# BLE-Shield-1_0_0-B.net
KiCad netlist of a schematic drawn in EAGLE
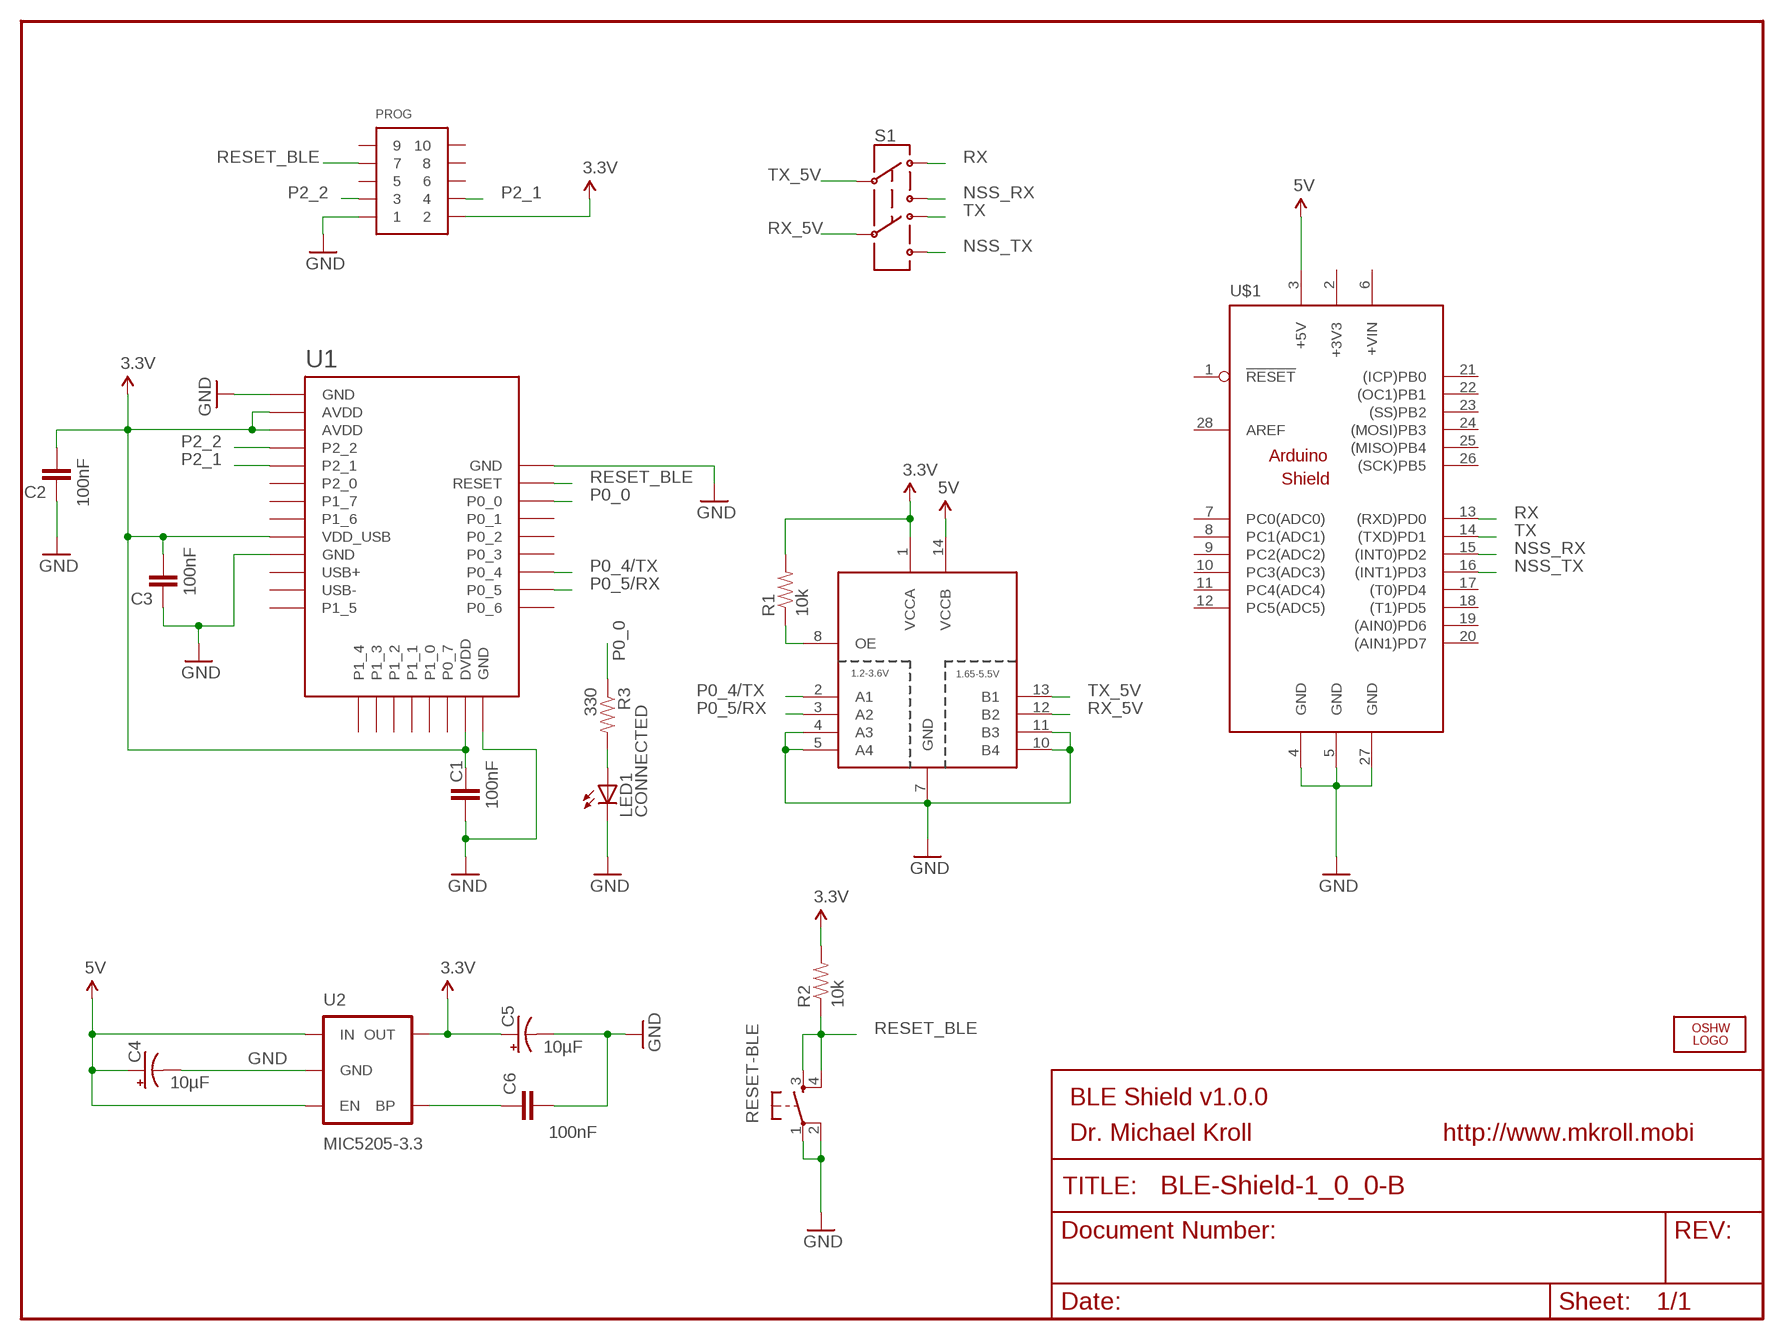
[diagram p0: schematic, sheet 1]

(export (version "E")
  (design (tool "Eeschema 10.0.6"))
  (components
    (comp (ref "C1")
      (value "100nF")
      (footprint "eagle-import:1206")
      (libsource (lib "eagle-import") (part "CAP1206"))
    )
    (comp (ref "C2")
      (value "100nF")
      (footprint "eagle-import:1206")
      (libsource (lib "eagle-import") (part "CAP1206"))
    )
    (comp (ref "C3")
      (value "100nF")
      (footprint "eagle-import:1206")
      (libsource (lib "eagle-import") (part "CAP1206"))
    )
    (comp (ref "C4")
      (value "10µF")
      (footprint "eagle-import:EIA3216")
      (libsource (lib "eagle-import") (part "CAP_POL1206"))
    )
    (comp (ref "C5")
      (value "10µF")
      (footprint "eagle-import:EIA3216")
      (libsource (lib "eagle-import") (part "CAP_POL1206"))
    )
    (comp (ref "C6")
      (value "100nF")
      (footprint "eagle-import:1206")
      (libsource (lib "eagle-import") (part "CAP1206"))
    )
    (comp (ref "LED1")
      (value "CONNECTED")
      (footprint "eagle-import:LED-1206-BLUE")
      (libsource (lib "eagle-import") (part "LED1206-BLUE"))
    )
    (comp (ref "LOGO1")
      (value "LOGO-OSHW-FILLX0200-NT")
      (footprint "eagle-import:OSHW_FILLX200_NOTEXT")
      (libsource (lib "eagle-import") (part "LOGO-OSHW-FILLX0200-NT"))
    )
    (comp (ref "PROG")
      (value "CONN_5-2-FTSH-V")
      (footprint "eagle-import:FTSH-105-DV")
      (libsource (lib "eagle-import") (part "CONN_5-2-FTSH-V"))
    )
    (comp (ref "R1")
      (value "10k")
      (footprint "eagle-import:0805")
      (libsource (lib "eagle-import") (part "RESISTOR0805-RES"))
    )
    (comp (ref "R2")
      (value "10k")
      (footprint "eagle-import:0805")
      (libsource (lib "eagle-import") (part "RESISTOR0805-RES"))
    )
    (comp (ref "R3")
      (value "330")
      (footprint "eagle-import:0805")
      (libsource (lib "eagle-import") (part "RESISTOR0805-RES"))
    )
    (comp (ref "RESET-BLE")
      (value "TAC_SWITCHSMD")
      (footprint "eagle-import:TACTILE_SWITCH_SMD")
      (libsource (lib "eagle-import") (part "TAC_SWITCHSMD"))
    )
    (comp (ref "S1")
      (value "SWITCH-DPDTSMD")
      (footprint "eagle-import:AYZ0202")
      (libsource (lib "eagle-import") (part "SWITCH-DPDTSMD"))
    )
    (comp (ref "U$1")
      (value "ARDUINO_SHIELD")
      (footprint "eagle-import:ARDUINO_SHIELD")
      (libsource (lib "eagle-import") (part "ARDUINO_SHIELD"))
    )
    (comp (ref "U1")
      (value "BLE112-A-VISUAL")
      (footprint "eagle-import:BLE112-A")
      (libsource (lib "eagle-import") (part "BLE112-A-VISUAL"))
    )
    (comp (ref "U2")
      (value "MIC5205-3.3")
      (footprint "eagle-import:SOT23-5")
      (libsource (lib "eagle-import") (part "V_REG_LDOSMD"))
    )
    (comp (ref "U3")
      (value "TXB0104DR")
      (footprint "eagle-import:SO14")
      (libsource (lib "eagle-import") (part "TXB0104DR"))
    )
  )
  (nets
    (net (code "1") (name "/+3V3") (class "Default")
      (node (ref "U$1") (pin "2") (pinfunction "+3V3_2") (pintype "power_in"))
    )
    (net (code "2") (name "/NSS_RX") (class "Default")
      (node (ref "S1") (pin "3") (pinfunction "3_3") (pintype "bidirectional"))
      (node (ref "U$1") (pin "15") (pinfunction "(INT0)PD2_15") (pintype "bidirectional"))
    )
    (net (code "3") (name "/NSS_TX") (class "Default")
      (node (ref "S1") (pin "6") (pinfunction "6_6") (pintype "bidirectional"))
      (node (ref "U$1") (pin "16") (pinfunction "(INT1)PD3_16") (pintype "bidirectional"))
    )
    (net (code "4") (name "/P0_0") (class "Default")
      (node (ref "R3") (pin "1") (pinfunction "1_1") (pintype "passive"))
      (node (ref "U1") (pin "P0_0") (pinfunction "P0_0_P0_0") (pintype "bidirectional"))
    )
    (net (code "5") (name "/P0_4{slash}TX") (class "Default")
      (node (ref "U1") (pin "P0_4") (pinfunction "P0_4_P0_4") (pintype "bidirectional"))
      (node (ref "U3") (pin "2") (pinfunction "A1_2") (pintype "bidirectional"))
    )
    (net (code "6") (name "/P0_5{slash}RX") (class "Default")
      (node (ref "U1") (pin "P0_5") (pinfunction "P0_5_P0_5") (pintype "bidirectional"))
      (node (ref "U3") (pin "3") (pinfunction "A2_3") (pintype "bidirectional"))
    )
    (net (code "7") (name "/P2_1") (class "Default")
      (node (ref "PROG") (pin "4") (pinfunction "4_4") (pintype "bidirectional"))
      (node (ref "U1") (pin "P2_1") (pinfunction "P2_1_P2_1") (pintype "bidirectional"))
    )
    (net (code "8") (name "/P2_2") (class "Default")
      (node (ref "PROG") (pin "3") (pinfunction "3_3") (pintype "bidirectional"))
      (node (ref "U1") (pin "P2_2") (pinfunction "P2_2_P2_2") (pintype "bidirectional"))
    )
    (net (code "9") (name "/RESET_BLE") (class "Default")
      (node (ref "PROG") (pin "7") (pinfunction "7_7") (pintype "bidirectional"))
      (node (ref "R2") (pin "1") (pinfunction "1_1") (pintype "passive"))
      (node (ref "RESET-BLE") (pin "3") (pinfunction "3_3") (pintype "passive"))
      (node (ref "RESET-BLE") (pin "4") (pinfunction "4_4") (pintype "passive"))
      (node (ref "U1") (pin "RESET") (pinfunction "RESET_RESET") (pintype "input"))
    )
    (net (code "10") (name "/RX") (class "Default")
      (node (ref "S1") (pin "1") (pinfunction "1_1") (pintype "bidirectional"))
      (node (ref "U$1") (pin "13") (pinfunction "(RXD)PD0_13") (pintype "bidirectional"))
    )
    (net (code "11") (name "/RX_5V") (class "Default")
      (node (ref "S1") (pin "5") (pinfunction "5_5") (pintype "bidirectional"))
      (node (ref "U3") (pin "12") (pinfunction "B2_12") (pintype "bidirectional"))
    )
    (net (code "12") (name "/TX") (class "Default")
      (node (ref "S1") (pin "4") (pinfunction "4_4") (pintype "bidirectional"))
      (node (ref "U$1") (pin "14") (pinfunction "(TXD)PD1_14") (pintype "bidirectional"))
    )
    (net (code "13") (name "/TX_5V") (class "Default")
      (node (ref "S1") (pin "2") (pinfunction "2_2") (pintype "bidirectional"))
      (node (ref "U3") (pin "13") (pinfunction "B1_13") (pintype "bidirectional"))
    )
    (net (code "14") (name "3.3V") (class "Default")
      (node (ref "C1") (pin "2") (pinfunction "2_2") (pintype "passive"))
      (node (ref "C2") (pin "2") (pinfunction "2_2") (pintype "passive"))
      (node (ref "C3") (pin "2") (pinfunction "2_2") (pintype "passive"))
      (node (ref "C5") (pin "A") (pinfunction "+_A") (pintype "passive"))
      (node (ref "PROG") (pin "2") (pinfunction "2_2") (pintype "bidirectional"))
      (node (ref "R1") (pin "2") (pinfunction "2_2") (pintype "passive"))
      (node (ref "R2") (pin "2") (pinfunction "2_2") (pintype "passive"))
      (node (ref "U1") (pin "AVDD1") (pinfunction "AVDD_AVDD1") (pintype "power_in"))
      (node (ref "U1") (pin "AVDD2") (pinfunction "AVDD_AVDD2") (pintype "power_in"))
      (node (ref "U1") (pin "DVDD") (pinfunction "DVDD_DVDD") (pintype "power_in"))
      (node (ref "U1") (pin "VDD_USB") (pinfunction "VDD_USB_VDD_USB") (pintype "power_in"))
      (node (ref "U2") (pin "5") (pinfunction "OUT_5") (pintype "passive"))
      (node (ref "U3") (pin "1") (pinfunction "VCCA_1") (pintype "bidirectional"))
    )
    (net (code "15") (name "5V") (class "Default")
      (node (ref "C4") (pin "A") (pinfunction "+_A") (pintype "passive"))
      (node (ref "U$1") (pin "3") (pinfunction "+5V_3") (pintype "power_in"))
      (node (ref "U2") (pin "1") (pinfunction "IN_1") (pintype "input"))
      (node (ref "U2") (pin "3") (pinfunction "EN_3") (pintype "input"))
      (node (ref "U3") (pin "14") (pinfunction "VCCB_14") (pintype "bidirectional"))
    )
    (net (code "16") (name "GND") (class "Default")
      (node (ref "C1") (pin "1") (pinfunction "1_1") (pintype "passive"))
      (node (ref "C2") (pin "1") (pinfunction "1_1") (pintype "passive"))
      (node (ref "C3") (pin "1") (pinfunction "1_1") (pintype "passive"))
      (node (ref "C4") (pin "C") (pinfunction "-_C") (pintype "passive"))
      (node (ref "C5") (pin "C") (pinfunction "-_C") (pintype "passive"))
      (node (ref "C6") (pin "2") (pinfunction "2_2") (pintype "passive"))
      (node (ref "LED1") (pin "C") (pinfunction "C_C") (pintype "passive"))
      (node (ref "PROG") (pin "1") (pinfunction "1_1") (pintype "bidirectional"))
      (node (ref "RESET-BLE") (pin "1") (pinfunction "1_1") (pintype "passive"))
      (node (ref "RESET-BLE") (pin "2") (pinfunction "2_2") (pintype "passive"))
      (node (ref "U$1") (pin "27") (pinfunction "GND_27") (pintype "power_in"))
      (node (ref "U$1") (pin "4") (pinfunction "GND_4") (pintype "power_in"))
      (node (ref "U$1") (pin "5") (pinfunction "GND_5") (pintype "power_in"))
      (node (ref "U1") (pin "GND1") (pinfunction "GND_GND1") (pintype "power_in"))
      (node (ref "U1") (pin "GND2") (pinfunction "GND_GND2") (pintype "power_in"))
      (node (ref "U1") (pin "GND3") (pinfunction "GND_GND3") (pintype "power_in"))
      (node (ref "U1") (pin "GND4") (pinfunction "GND_GND4") (pintype "power_in"))
      (node (ref "U2") (pin "2") (pinfunction "GND_2") (pintype "input"))
      (node (ref "U3") (pin "10") (pinfunction "B4_10") (pintype "bidirectional"))
      (node (ref "U3") (pin "11") (pinfunction "B3_11") (pintype "bidirectional"))
      (node (ref "U3") (pin "4") (pinfunction "A3_4") (pintype "bidirectional"))
      (node (ref "U3") (pin "5") (pinfunction "A4_5") (pintype "bidirectional"))
      (node (ref "U3") (pin "7") (pinfunction "GND_7") (pintype "bidirectional"))
    )
    (net (code "17") (name "Net-(LED1-PadA)") (class "Default")
      (node (ref "LED1") (pin "A") (pinfunction "A_A") (pintype "passive"))
      (node (ref "R3") (pin "2") (pinfunction "2_2") (pintype "passive"))
    )
    (net (code "18") (name "Net-(U2-BP)") (class "Default")
      (node (ref "C6") (pin "1") (pinfunction "1_1") (pintype "passive"))
      (node (ref "U2") (pin "4") (pinfunction "BP_4") (pintype "input"))
    )
    (net (code "19") (name "Net-(U3-OE)") (class "Default")
      (node (ref "R1") (pin "1") (pinfunction "1_1") (pintype "passive"))
      (node (ref "U3") (pin "8") (pinfunction "OE_8") (pintype "bidirectional"))
    )
    (net (code "20") (name "unconnected-(PROG-Pad5)") (class "Default")
      (node (ref "PROG") (pin "5") (pinfunction "5_5") (pintype "bidirectional"))
    )
    (net (code "21") (name "unconnected-(PROG-Pad6)") (class "Default")
      (node (ref "PROG") (pin "6") (pinfunction "6_6") (pintype "bidirectional"))
    )
    (net (code "22") (name "unconnected-(PROG-Pad8)") (class "Default")
      (node (ref "PROG") (pin "8") (pinfunction "8_8") (pintype "bidirectional"))
    )
    (net (code "23") (name "unconnected-(PROG-Pad9)") (class "Default")
      (node (ref "PROG") (pin "9") (pinfunction "9_9") (pintype "bidirectional"))
    )
    (net (code "24") (name "unconnected-(PROG-Pad10)") (class "Default")
      (node (ref "PROG") (pin "10") (pinfunction "10_10") (pintype "bidirectional"))
    )
    (net (code "25") (name "unconnected-(U$1-(AIN0)PD6-Pad19)") (class "Default")
      (node (ref "U$1") (pin "19") (pinfunction "(AIN0)PD6_19") (pintype "bidirectional"))
    )
    (net (code "26") (name "unconnected-(U$1-(AIN1)PD7-Pad20)") (class "Default")
      (node (ref "U$1") (pin "20") (pinfunction "(AIN1)PD7_20") (pintype "bidirectional"))
    )
    (net (code "27") (name "unconnected-(U$1-(ICP)PB0-Pad21)") (class "Default")
      (node (ref "U$1") (pin "21") (pinfunction "(ICP)PB0_21") (pintype "bidirectional"))
    )
    (net (code "28") (name "unconnected-(U$1-(MISO)PB4-Pad25)") (class "Default")
      (node (ref "U$1") (pin "25") (pinfunction "(MISO)PB4_25") (pintype "bidirectional"))
    )
    (net (code "29") (name "unconnected-(U$1-(MOSI)PB3-Pad24)") (class "Default")
      (node (ref "U$1") (pin "24") (pinfunction "(MOSI)PB3_24") (pintype "bidirectional"))
    )
    (net (code "30") (name "unconnected-(U$1-(OC1)PB1-Pad22)") (class "Default")
      (node (ref "U$1") (pin "22") (pinfunction "(OC1)PB1_22") (pintype "bidirectional"))
    )
    (net (code "31") (name "unconnected-(U$1-(SCK)PB5-Pad26)") (class "Default")
      (node (ref "U$1") (pin "26") (pinfunction "(SCK)PB5_26") (pintype "bidirectional"))
    )
    (net (code "32") (name "unconnected-(U$1-(SS)PB2-Pad23)") (class "Default")
      (node (ref "U$1") (pin "23") (pinfunction "(SS)PB2_23") (pintype "bidirectional"))
    )
    (net (code "33") (name "unconnected-(U$1-(T0)PD4-Pad17)") (class "Default")
      (node (ref "U$1") (pin "17") (pinfunction "(T0)PD4_17") (pintype "bidirectional"))
    )
    (net (code "34") (name "unconnected-(U$1-(T1)PD5-Pad18)") (class "Default")
      (node (ref "U$1") (pin "18") (pinfunction "(T1)PD5_18") (pintype "bidirectional"))
    )
    (net (code "35") (name "unconnected-(U$1-+VIN-Pad6)") (class "Default")
      (node (ref "U$1") (pin "6") (pinfunction "+VIN_6") (pintype "bidirectional"))
    )
    (net (code "36") (name "unconnected-(U$1-AREF-Pad28)") (class "Default")
      (node (ref "U$1") (pin "28") (pinfunction "AREF_28") (pintype "bidirectional"))
    )
    (net (code "37") (name "unconnected-(U$1-PC0(ADC0)-Pad7)") (class "Default")
      (node (ref "U$1") (pin "7") (pinfunction "PC0(ADC0)_7") (pintype "bidirectional"))
    )
    (net (code "38") (name "unconnected-(U$1-PC1(ADC1)-Pad8)") (class "Default")
      (node (ref "U$1") (pin "8") (pinfunction "PC1(ADC1)_8") (pintype "bidirectional"))
    )
    (net (code "39") (name "unconnected-(U$1-PC2(ADC2)-Pad9)") (class "Default")
      (node (ref "U$1") (pin "9") (pinfunction "PC2(ADC2)_9") (pintype "bidirectional"))
    )
    (net (code "40") (name "unconnected-(U$1-PC3(ADC3)-Pad10)") (class "Default")
      (node (ref "U$1") (pin "10") (pinfunction "PC3(ADC3)_10") (pintype "bidirectional"))
    )
    (net (code "41") (name "unconnected-(U$1-PC4(ADC4)-Pad11)") (class "Default")
      (node (ref "U$1") (pin "11") (pinfunction "PC4(ADC4)_11") (pintype "bidirectional"))
    )
    (net (code "42") (name "unconnected-(U$1-PC5(ADC5)-Pad12)") (class "Default")
      (node (ref "U$1") (pin "12") (pinfunction "PC5(ADC5)_12") (pintype "bidirectional"))
    )
    (net (code "43") (name "unconnected-(U$1-~{RESET}-Pad1)") (class "Default")
      (node (ref "U$1") (pin "1") (pinfunction "~{RESET}_1") (pintype "bidirectional"))
    )
    (net (code "44") (name "unconnected-(U1-PadP0_1)") (class "Default")
      (node (ref "U1") (pin "P0_1") (pinfunction "P0_1_P0_1") (pintype "bidirectional"))
    )
    (net (code "45") (name "unconnected-(U1-PadP0_2)") (class "Default")
      (node (ref "U1") (pin "P0_2") (pinfunction "P0_2_P0_2") (pintype "bidirectional"))
    )
    (net (code "46") (name "unconnected-(U1-PadP0_3)") (class "Default")
      (node (ref "U1") (pin "P0_3") (pinfunction "P0_3_P0_3") (pintype "bidirectional"))
    )
    (net (code "47") (name "unconnected-(U1-PadP0_6)") (class "Default")
      (node (ref "U1") (pin "P0_6") (pinfunction "P0_6_P0_6") (pintype "bidirectional"))
    )
    (net (code "48") (name "unconnected-(U1-PadP0_7)") (class "Default")
      (node (ref "U1") (pin "P0_7") (pinfunction "P0_7_P0_7") (pintype "bidirectional"))
    )
    (net (code "49") (name "unconnected-(U1-PadP1_0)") (class "Default")
      (node (ref "U1") (pin "P1_0") (pinfunction "P1_0_P1_0") (pintype "bidirectional"))
    )
    (net (code "50") (name "unconnected-(U1-PadP1_1)") (class "Default")
      (node (ref "U1") (pin "P1_1") (pinfunction "P1_1_P1_1") (pintype "bidirectional"))
    )
    (net (code "51") (name "unconnected-(U1-PadP1_2)") (class "Default")
      (node (ref "U1") (pin "P1_2") (pinfunction "P1_2_P1_2") (pintype "bidirectional"))
    )
    (net (code "52") (name "unconnected-(U1-PadP1_3)") (class "Default")
      (node (ref "U1") (pin "P1_3") (pinfunction "P1_3_P1_3") (pintype "bidirectional"))
    )
    (net (code "53") (name "unconnected-(U1-PadP1_4)") (class "Default")
      (node (ref "U1") (pin "P1_4") (pinfunction "P1_4_P1_4") (pintype "bidirectional"))
    )
    (net (code "54") (name "unconnected-(U1-PadP1_5)") (class "Default")
      (node (ref "U1") (pin "P1_5") (pinfunction "P1_5_P1_5") (pintype "bidirectional"))
    )
    (net (code "55") (name "unconnected-(U1-PadP1_6)") (class "Default")
      (node (ref "U1") (pin "P1_6") (pinfunction "P1_6_P1_6") (pintype "bidirectional"))
    )
    (net (code "56") (name "unconnected-(U1-PadP1_7)") (class "Default")
      (node (ref "U1") (pin "P1_7") (pinfunction "P1_7_P1_7") (pintype "bidirectional"))
    )
    (net (code "57") (name "unconnected-(U1-PadP2_0)") (class "Default")
      (node (ref "U1") (pin "P2_0") (pinfunction "P2_0_P2_0") (pintype "bidirectional"))
    )
    (net (code "58") (name "unconnected-(U1-PadUSB+)") (class "Default")
      (node (ref "U1") (pin "USB+") (pinfunction "USB+_USB+") (pintype "bidirectional"))
    )
    (net (code "59") (name "unconnected-(U1-PadUSB-)") (class "Default")
      (node (ref "U1") (pin "USB-") (pinfunction "USB-_USB-") (pintype "bidirectional"))
    )
  )
)
